# PCB-2x8GPIO.net
KiCad netlist of a schematic drawn in EAGLE
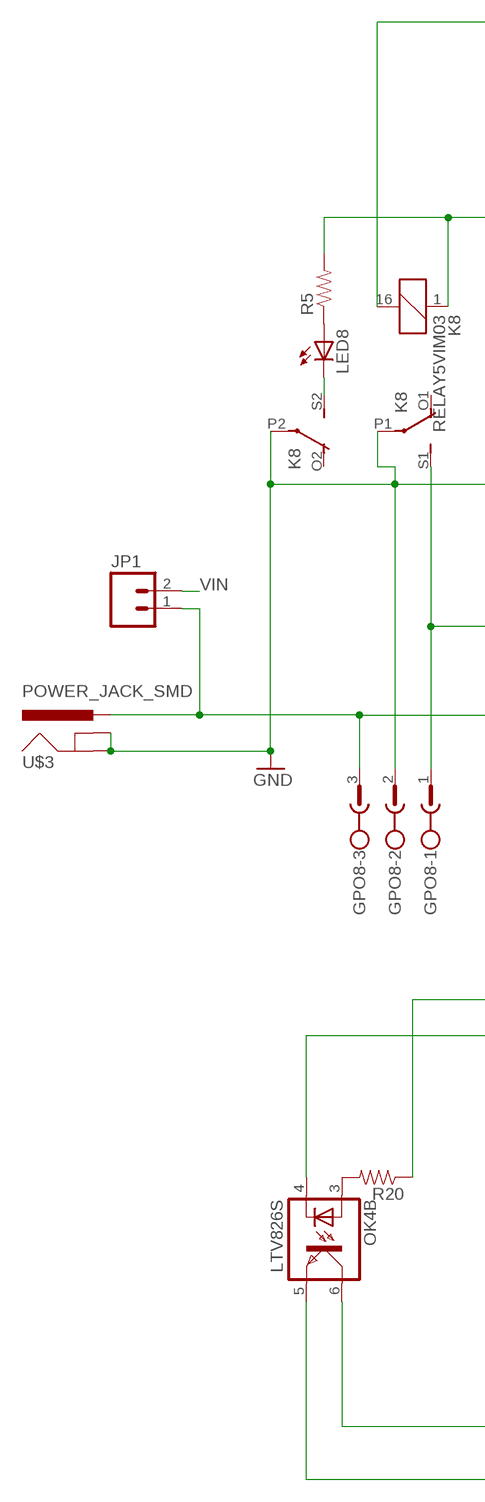
[diagram p0: schematic, sheet 1, part 1 of 2]
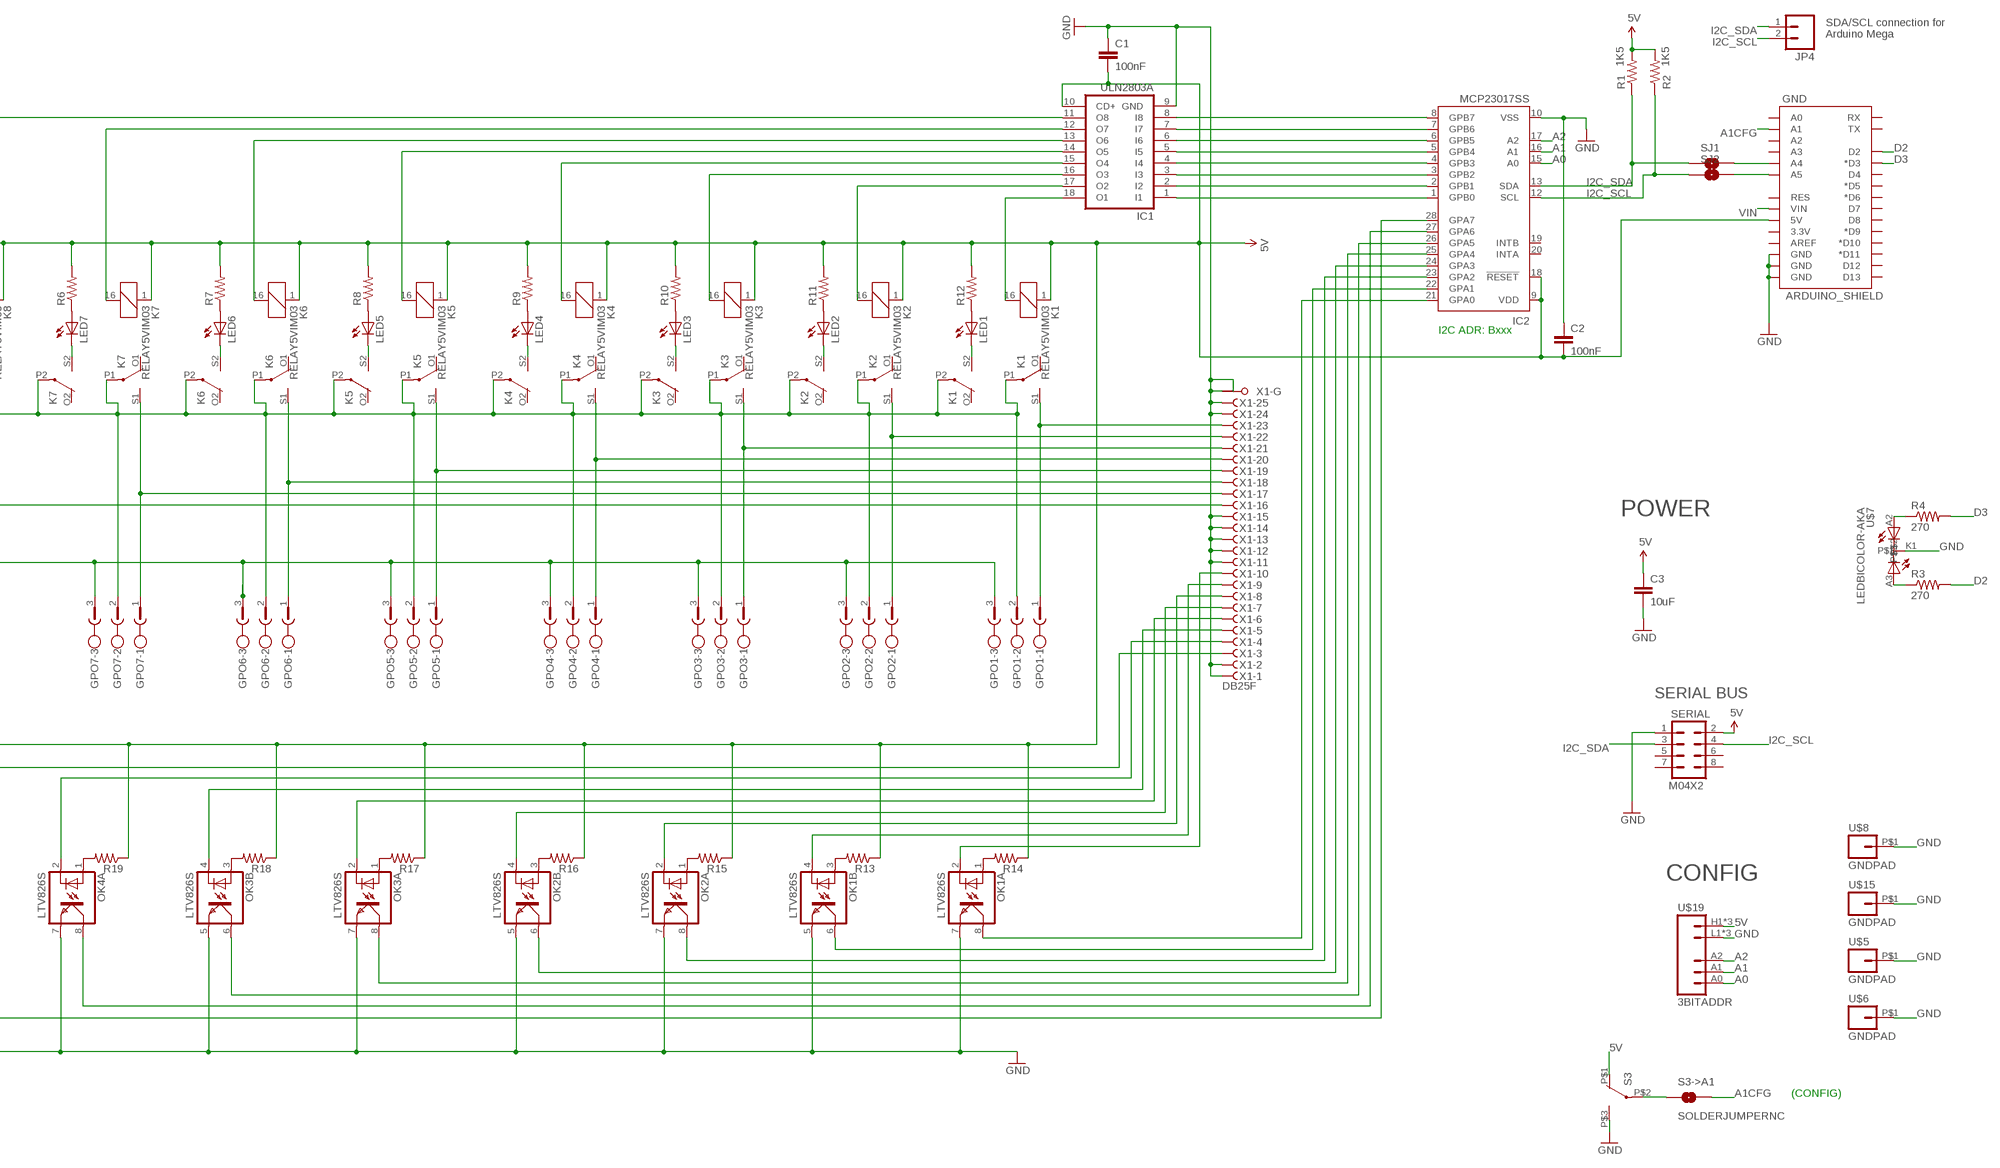
[diagram p1: schematic, sheet 1, part 2 of 2]

(export (version "E")
  (design (tool "Eeschema 10.0.6"))
  (components
    (comp (ref "C1")
      (value "100nF")
      (footprint "eagle-import:0805")
      (libsource (lib "eagle-import") (part "CAP0805"))
    )
    (comp (ref "C2")
      (value "100nF")
      (footprint "eagle-import:0603-CAP")
      (libsource (lib "eagle-import") (part "CAP0603-CAP"))
    )
    (comp (ref "C3")
      (value "10uF")
      (footprint "eagle-import:0805")
      (libsource (lib "eagle-import") (part "CAP0805"))
    )
    (comp (ref "GND")
      (value "ARDUINO_SHIELD")
      (footprint "eagle-import:ARDUINO_BOXSHIELD_NOHOLES")
      (libsource (lib "eagle-import") (part "ARDUINO_SHIELD"))
    )
    (comp (ref "GPO1")
      (value "CON1")
      (footprint "eagle-import:MSTBV3")
      (fields (field (name "MPN") "MSTBV 2,5/3-GF-5.08"))
      (libsource (lib "eagle-import") (part "MSTBV3"))
    )
    (comp (ref "GPO2")
      (value "CON1")
      (footprint "eagle-import:MSTBV3")
      (fields (field (name "MPN") "MSTBV 2,5/3-GF-5.08"))
      (libsource (lib "eagle-import") (part "MSTBV3"))
    )
    (comp (ref "GPO3")
      (value "CON1")
      (footprint "eagle-import:MSTBV3")
      (fields (field (name "MPN") "MSTBV 2,5/3-GF-5.08"))
      (libsource (lib "eagle-import") (part "MSTBV3"))
    )
    (comp (ref "GPO4")
      (value "CON1")
      (footprint "eagle-import:MSTBV3")
      (fields (field (name "MPN") "MSTBV 2,5/3-GF-5.08"))
      (libsource (lib "eagle-import") (part "MSTBV3"))
    )
    (comp (ref "GPO5")
      (value "CON1")
      (footprint "eagle-import:MSTBV3")
      (fields (field (name "MPN") "MSTBV 2,5/3-GF-5.08"))
      (libsource (lib "eagle-import") (part "MSTBV3"))
    )
    (comp (ref "GPO6")
      (value "CON1")
      (footprint "eagle-import:MSTBV3")
      (fields (field (name "MPN") "MSTBV 2,5/3-GF-5.08"))
      (libsource (lib "eagle-import") (part "MSTBV3"))
    )
    (comp (ref "GPO7")
      (value "CON1")
      (footprint "eagle-import:MSTBV3")
      (fields (field (name "MPN") "MSTBV 2,5/3-GF-5.08"))
      (libsource (lib "eagle-import") (part "MSTBV3"))
    )
    (comp (ref "GPO8")
      (value "GPO8")
      (footprint "eagle-import:MSTBV3")
      (fields (field (name "MPN") "MSTBV 2,5/3-GF-5.08"))
      (libsource (lib "eagle-import") (part "MSTBV3"))
    )
    (comp (ref "IC1")
      (value "ULN2803A")
      (footprint "eagle-import:SO18W")
      (libsource (lib "eagle-import") (part "ULN2803ASO18W"))
    )
    (comp (ref "IC2")
      (value "MCP23017SS")
      (footprint "eagle-import:SSOP28")
      (fields (field (name "MF") "MICROCHIP") (field (name "MPN") "MCP23017-E/SS"))
      (libsource (lib "eagle-import") (part "MCP23017SS"))
    )
    (comp (ref "JP1")
      (value "M02LOCK")
      (footprint "eagle-import:1X02_LOCK")
      (libsource (lib "eagle-import") (part "M02LOCK"))
    )
    (comp (ref "JP4")
      (value "M02PTH")
      (footprint "eagle-import:1X02")
      (libsource (lib "eagle-import") (part "M02PTH"))
    )
    (comp (ref "K1")
      (value "RELAY5VIM03")
      (footprint "eagle-import:DS2Y")
      (libsource (lib "eagle-import") (part "RELAY5VIM03"))
    )
    (comp (ref "K2")
      (value "RELAY5VIM03")
      (footprint "eagle-import:DS2Y")
      (libsource (lib "eagle-import") (part "RELAY5VIM03"))
    )
    (comp (ref "K3")
      (value "RELAY5VIM03")
      (footprint "eagle-import:DS2Y")
      (libsource (lib "eagle-import") (part "RELAY5VIM03"))
    )
    (comp (ref "K4")
      (value "RELAY5VIM03")
      (footprint "eagle-import:DS2Y")
      (libsource (lib "eagle-import") (part "RELAY5VIM03"))
    )
    (comp (ref "K5")
      (value "RELAY5VIM03")
      (footprint "eagle-import:DS2Y")
      (libsource (lib "eagle-import") (part "RELAY5VIM03"))
    )
    (comp (ref "K6")
      (value "RELAY5VIM03")
      (footprint "eagle-import:DS2Y")
      (libsource (lib "eagle-import") (part "RELAY5VIM03"))
    )
    (comp (ref "K7")
      (value "RELAY5VIM03")
      (footprint "eagle-import:DS2Y")
      (libsource (lib "eagle-import") (part "RELAY5VIM03"))
    )
    (comp (ref "K8")
      (value "RELAY5VIM03")
      (footprint "eagle-import:DS2Y")
      (libsource (lib "eagle-import") (part "RELAY5VIM03"))
    )
    (comp (ref "LED1")
      (value "LED1206")
      (footprint "eagle-import:LED-1206")
      (libsource (lib "eagle-import") (part "LED1206"))
    )
    (comp (ref "LED2")
      (value "LED1206")
      (footprint "eagle-import:LED-1206")
      (libsource (lib "eagle-import") (part "LED1206"))
    )
    (comp (ref "LED3")
      (value "LED1206")
      (footprint "eagle-import:LED-1206")
      (libsource (lib "eagle-import") (part "LED1206"))
    )
    (comp (ref "LED4")
      (value "LED1206")
      (footprint "eagle-import:LED-1206")
      (libsource (lib "eagle-import") (part "LED1206"))
    )
    (comp (ref "LED5")
      (value "LED1206")
      (footprint "eagle-import:LED-1206")
      (libsource (lib "eagle-import") (part "LED1206"))
    )
    (comp (ref "LED6")
      (value "LED1206")
      (footprint "eagle-import:LED-1206")
      (libsource (lib "eagle-import") (part "LED1206"))
    )
    (comp (ref "LED7")
      (value "LED1206")
      (footprint "eagle-import:LED-1206")
      (libsource (lib "eagle-import") (part "LED1206"))
    )
    (comp (ref "LED8")
      (value "LED1206")
      (footprint "eagle-import:LED-1206")
      (libsource (lib "eagle-import") (part "LED1206"))
    )
    (comp (ref "OK1")
      (value "LTV826S")
      (footprint "eagle-import:DIL8-SMD")
      (libsource (lib "eagle-import") (part "LTV826S"))
    )
    (comp (ref "OK2")
      (value "LTV826S")
      (footprint "eagle-import:DIL8-SMD")
      (libsource (lib "eagle-import") (part "LTV826S"))
    )
    (comp (ref "OK3")
      (value "LTV826S")
      (footprint "eagle-import:DIL8-SMD")
      (libsource (lib "eagle-import") (part "LTV826S"))
    )
    (comp (ref "OK4")
      (value "LTV826S")
      (footprint "eagle-import:DIL8-SMD")
      (libsource (lib "eagle-import") (part "LTV826S"))
    )
    (comp (ref "R1")
      (value "1K5")
      (footprint "eagle-import:0603-RES")
      (libsource (lib "eagle-import") (part "RESISTOR0603-RES"))
    )
    (comp (ref "R2")
      (value "1K5")
      (footprint "eagle-import:0603-RES")
      (libsource (lib "eagle-import") (part "RESISTOR0603-RES"))
    )
    (comp (ref "R3")
      (value "270")
      (footprint "eagle-import:0603-RES")
      (libsource (lib "eagle-import") (part "RESISTOR0603-RES"))
    )
    (comp (ref "R4")
      (value "270")
      (footprint "eagle-import:0603-RES")
      (libsource (lib "eagle-import") (part "RESISTOR0603-RES"))
    )
    (comp (ref "R5")
      (value "RESISTOR0603-RES")
      (footprint "eagle-import:0603-RES")
      (libsource (lib "eagle-import") (part "RESISTOR0603-RES"))
    )
    (comp (ref "R6")
      (value "RESISTOR0603-RES")
      (footprint "eagle-import:0603-RES")
      (libsource (lib "eagle-import") (part "RESISTOR0603-RES"))
    )
    (comp (ref "R7")
      (value "RESISTOR0603-RES")
      (footprint "eagle-import:0603-RES")
      (libsource (lib "eagle-import") (part "RESISTOR0603-RES"))
    )
    (comp (ref "R8")
      (value "RESISTOR0603-RES")
      (footprint "eagle-import:0603-RES")
      (libsource (lib "eagle-import") (part "RESISTOR0603-RES"))
    )
    (comp (ref "R9")
      (value "RESISTOR0603-RES")
      (footprint "eagle-import:0603-RES")
      (libsource (lib "eagle-import") (part "RESISTOR0603-RES"))
    )
    (comp (ref "R10")
      (value "RESISTOR0603-RES")
      (footprint "eagle-import:0603-RES")
      (libsource (lib "eagle-import") (part "RESISTOR0603-RES"))
    )
    (comp (ref "R11")
      (value "RESISTOR0603-RES")
      (footprint "eagle-import:0603-RES")
      (libsource (lib "eagle-import") (part "RESISTOR0603-RES"))
    )
    (comp (ref "R12")
      (value "RESISTOR0603-RES")
      (footprint "eagle-import:0603-RES")
      (libsource (lib "eagle-import") (part "RESISTOR0603-RES"))
    )
    (comp (ref "R13")
      (value "RESISTOR0603-RES")
      (footprint "eagle-import:0603-RES")
      (libsource (lib "eagle-import") (part "RESISTOR0603-RES"))
    )
    (comp (ref "R14")
      (value "RESISTOR0603-RES")
      (footprint "eagle-import:0603-RES")
      (libsource (lib "eagle-import") (part "RESISTOR0603-RES"))
    )
    (comp (ref "R15")
      (value "RESISTOR0603-RES")
      (footprint "eagle-import:0603-RES")
      (libsource (lib "eagle-import") (part "RESISTOR0603-RES"))
    )
    (comp (ref "R16")
      (value "RESISTOR0603-RES")
      (footprint "eagle-import:0603-RES")
      (libsource (lib "eagle-import") (part "RESISTOR0603-RES"))
    )
    (comp (ref "R17")
      (value "RESISTOR0603-RES")
      (footprint "eagle-import:0603-RES")
      (libsource (lib "eagle-import") (part "RESISTOR0603-RES"))
    )
    (comp (ref "R18")
      (value "RESISTOR0603-RES")
      (footprint "eagle-import:0603-RES")
      (libsource (lib "eagle-import") (part "RESISTOR0603-RES"))
    )
    (comp (ref "R19")
      (value "RESISTOR0603-RES")
      (footprint "eagle-import:0603-RES")
      (libsource (lib "eagle-import") (part "RESISTOR0603-RES"))
    )
    (comp (ref "R20")
      (value "RESISTOR0603-RES")
      (footprint "eagle-import:0603-RES")
      (libsource (lib "eagle-import") (part "RESISTOR0603-RES"))
    )
    (comp (ref "S3")
      (value "CFG")
      (footprint "eagle-import:TECONNECTIVITY-DPST")
      (libsource (lib "eagle-import") (part "SWITCH-DPST"))
    )
    (comp (ref "S3->A1")
      (value "SOLDERJUMPERNC")
      (footprint "eagle-import:SJ_2S")
      (libsource (lib "eagle-import") (part "SOLDERJUMPERNC"))
    )
    (comp (ref "SERIAL")
      (value "M04X2")
      (footprint "eagle-import:2X4")
      (libsource (lib "eagle-import") (part "M04X2"))
    )
    (comp (ref "SJ1")
      (value "SOLDERJUMPERNC")
      (footprint "eagle-import:SJ_2S")
      (libsource (lib "eagle-import") (part "SOLDERJUMPERNC"))
    )
    (comp (ref "SJ2")
      (value "SOLDERJUMPERNC")
      (footprint "eagle-import:SJ_2S")
      (libsource (lib "eagle-import") (part "SOLDERJUMPERNC"))
    )
    (comp (ref "U$3")
      (value "POWER_JACK_SMD")
      (footprint "eagle-import:POWER_JACK_SMD")
      (libsource (lib "eagle-import") (part "POWER_JACK_SMD"))
    )
    (comp (ref "U$5")
      (value "GNDPAD")
      (footprint "eagle-import:3.2MMPAD")
      (libsource (lib "eagle-import") (part "GNDPAD"))
    )
    (comp (ref "U$6")
      (value "GNDPAD")
      (footprint "eagle-import:3.2MMPAD")
      (libsource (lib "eagle-import") (part "GNDPAD"))
    )
    (comp (ref "U$7")
      (value "LEDBICOLOR-AKA")
      (footprint "eagle-import:LED5MM-BICOLOR")
      (libsource (lib "eagle-import") (part "LEDBICOLOR-AKA"))
    )
    (comp (ref "U$8")
      (value "GNDPAD")
      (footprint "eagle-import:3.2MMPAD")
      (libsource (lib "eagle-import") (part "GNDPAD"))
    )
    (comp (ref "U$15")
      (value "GNDPAD")
      (footprint "eagle-import:3.2MMPAD")
      (libsource (lib "eagle-import") (part "GNDPAD"))
    )
    (comp (ref "U$19")
      (value "3BITADDR")
      (footprint "eagle-import:3BITADDR")
      (libsource (lib "eagle-import") (part "3BITADDR"))
    )
    (comp (ref "X1")
      (value "DB25F")
      (footprint "eagle-import:F25HP")
      (libsource (lib "eagle-import") (part "F25HPS"))
    )
  )
  (nets
    (net (code "1") (name "/A0") (class "Default")
      (node (ref "IC2") (pin "15") (pinfunction "A0_15") (pintype "input"))
      (node (ref "U$19") (pin "A0") (pinfunction "A0_A0") (pintype "passive"))
    )
    (net (code "2") (name "/A1") (class "Default")
      (node (ref "IC2") (pin "16") (pinfunction "A1_16") (pintype "input"))
      (node (ref "U$19") (pin "A1") (pinfunction "A1_A1") (pintype "passive"))
    )
    (net (code "3") (name "/A1CFG") (class "Default")
      (node (ref "GND") (pin "A1") (pinfunction "A1_A1") (pintype "bidirectional"))
      (node (ref "S3->A1") (pin "2") (pinfunction "2_2") (pintype "passive"))
    )
    (net (code "4") (name "/A2") (class "Default")
      (node (ref "IC2") (pin "17") (pinfunction "A2_17") (pintype "input"))
      (node (ref "U$19") (pin "A2") (pinfunction "A2_A2") (pintype "passive"))
    )
    (net (code "5") (name "/D2") (class "Default")
      (node (ref "GND") (pin "2") (pinfunction "D2_2") (pintype "bidirectional"))
      (node (ref "R3") (pin "2") (pinfunction "2_2") (pintype "passive"))
    )
    (net (code "6") (name "/D3") (class "Default")
      (node (ref "GND") (pin "3") (pinfunction "*D3_3") (pintype "bidirectional"))
      (node (ref "R4") (pin "2") (pinfunction "2_2") (pintype "passive"))
    )
    (net (code "7") (name "/I2C_SCL") (class "Default")
      (node (ref "IC2") (pin "12") (pinfunction "SCL_12") (pintype "input"))
      (node (ref "JP4") (pin "2") (pinfunction "2_2") (pintype "passive"))
      (node (ref "R2") (pin "1") (pinfunction "1_1") (pintype "passive"))
      (node (ref "SERIAL") (pin "4") (pinfunction "4_4") (pintype "passive"))
      (node (ref "SJ2") (pin "1") (pinfunction "1_1") (pintype "passive"))
    )
    (net (code "8") (name "/I2C_SDA") (class "Default")
      (node (ref "IC2") (pin "13") (pinfunction "SDA_13") (pintype "bidirectional"))
      (node (ref "JP4") (pin "1") (pinfunction "1_1") (pintype "passive"))
      (node (ref "R1") (pin "1") (pinfunction "1_1") (pintype "passive"))
      (node (ref "SERIAL") (pin "3") (pinfunction "3_3") (pintype "passive"))
      (node (ref "SJ1") (pin "1") (pinfunction "1_1") (pintype "passive"))
    )
    (net (code "9") (name "/VIN") (class "Default")
      (node (ref "GND") (pin "VIN") (pinfunction "VIN_VIN") (pintype "bidirectional"))
      (node (ref "JP1") (pin "2") (pinfunction "2_2") (pintype "passive"))
    )
    (net (code "10") (name "5V") (class "Default")
      (node (ref "C1") (pin "2") (pinfunction "2_2") (pintype "passive"))
      (node (ref "C2") (pin "2") (pinfunction "2_2") (pintype "passive"))
      (node (ref "C3") (pin "1") (pinfunction "1_1") (pintype "passive"))
      (node (ref "GND") (pin "5V@0") (pinfunction "5V_5V@0") (pintype "bidirectional"))
      (node (ref "IC1") (pin "10") (pinfunction "CD+_10") (pintype "passive"))
      (node (ref "IC2") (pin "18") (pinfunction "~{RESET}_18") (pintype "input"))
      (node (ref "IC2") (pin "9") (pinfunction "VDD_9") (pintype "power_in"))
      (node (ref "K1") (pin "1") (pinfunction "1_1") (pintype "passive"))
      (node (ref "K2") (pin "1") (pinfunction "1_1") (pintype "passive"))
      (node (ref "K3") (pin "1") (pinfunction "1_1") (pintype "passive"))
      (node (ref "K4") (pin "1") (pinfunction "1_1") (pintype "passive"))
      (node (ref "K5") (pin "1") (pinfunction "1_1") (pintype "passive"))
      (node (ref "K6") (pin "1") (pinfunction "1_1") (pintype "passive"))
      (node (ref "K7") (pin "1") (pinfunction "1_1") (pintype "passive"))
      (node (ref "K8") (pin "1") (pinfunction "1_1") (pintype "passive"))
      (node (ref "R1") (pin "2") (pinfunction "2_2") (pintype "passive"))
      (node (ref "R10") (pin "2") (pinfunction "2_2") (pintype "passive"))
      (node (ref "R11") (pin "2") (pinfunction "2_2") (pintype "passive"))
      (node (ref "R12") (pin "2") (pinfunction "2_2") (pintype "passive"))
      (node (ref "R13") (pin "1") (pinfunction "1_1") (pintype "passive"))
      (node (ref "R14") (pin "1") (pinfunction "1_1") (pintype "passive"))
      (node (ref "R15") (pin "1") (pinfunction "1_1") (pintype "passive"))
      (node (ref "R16") (pin "1") (pinfunction "1_1") (pintype "passive"))
      (node (ref "R17") (pin "1") (pinfunction "1_1") (pintype "passive"))
      (node (ref "R18") (pin "1") (pinfunction "1_1") (pintype "passive"))
      (node (ref "R19") (pin "1") (pinfunction "1_1") (pintype "passive"))
      (node (ref "R2") (pin "2") (pinfunction "2_2") (pintype "passive"))
      (node (ref "R20") (pin "1") (pinfunction "1_1") (pintype "passive"))
      (node (ref "R5") (pin "2") (pinfunction "2_2") (pintype "passive"))
      (node (ref "R6") (pin "2") (pinfunction "2_2") (pintype "passive"))
      (node (ref "R7") (pin "2") (pinfunction "2_2") (pintype "passive"))
      (node (ref "R8") (pin "2") (pinfunction "2_2") (pintype "passive"))
      (node (ref "R9") (pin "2") (pinfunction "2_2") (pintype "passive"))
      (node (ref "S3") (pin "P$1") (pinfunction "O_P$1") (pintype "passive"))
      (node (ref "SERIAL") (pin "2") (pinfunction "2_2") (pintype "passive"))
      (node (ref "U$19") (pin "H1") (pinfunction "VCC_H1") (pintype "passive"))
      (node (ref "U$19") (pin "H2") (pinfunction "VCC_H2") (pintype "passive"))
      (node (ref "U$19") (pin "H3") (pinfunction "VCC_H3") (pintype "passive"))
    )
    (net (code "11") (name "GND") (class "Default")
      (node (ref "C1") (pin "1") (pinfunction "1_1") (pintype "passive"))
      (node (ref "C2") (pin "1") (pinfunction "1_1") (pintype "passive"))
      (node (ref "C3") (pin "2") (pinfunction "2_2") (pintype "passive"))
      (node (ref "GND") (pin "GND@0") (pinfunction "GND_GND@0") (pintype "bidirectional"))
      (node (ref "GND") (pin "GND@1") (pinfunction "GND_GND@1") (pintype "bidirectional"))
      (node (ref "GND") (pin "GND@4") (pinfunction "GND_GND@4") (pintype "bidirectional"))
      (node (ref "GPO1") (pin "2") (pinfunction "1_2") (pintype "passive"))
      (node (ref "GPO2") (pin "2") (pinfunction "1_2") (pintype "passive"))
      (node (ref "GPO3") (pin "2") (pinfunction "1_2") (pintype "passive"))
      (node (ref "GPO4") (pin "2") (pinfunction "1_2") (pintype "passive"))
      (node (ref "GPO5") (pin "2") (pinfunction "1_2") (pintype "passive"))
      (node (ref "GPO6") (pin "2") (pinfunction "1_2") (pintype "passive"))
      (node (ref "GPO7") (pin "2") (pinfunction "1_2") (pintype "passive"))
      (node (ref "GPO8") (pin "2") (pinfunction "1_2") (pintype "passive"))
      (node (ref "IC1") (pin "9") (pinfunction "GND_9") (pintype "power_in"))
      (node (ref "IC2") (pin "10") (pinfunction "VSS_10") (pintype "power_in"))
      (node (ref "K1") (pin "P1") (pinfunction "P_P1") (pintype "passive"))
      (node (ref "K1") (pin "P2") (pinfunction "P_P2") (pintype "passive"))
      (node (ref "K2") (pin "P1") (pinfunction "P_P1") (pintype "passive"))
      (node (ref "K2") (pin "P2") (pinfunction "P_P2") (pintype "passive"))
      (node (ref "K3") (pin "P1") (pinfunction "P_P1") (pintype "passive"))
      (node (ref "K3") (pin "P2") (pinfunction "P_P2") (pintype "passive"))
      (node (ref "K4") (pin "P1") (pinfunction "P_P1") (pintype "passive"))
      (node (ref "K4") (pin "P2") (pinfunction "P_P2") (pintype "passive"))
      (node (ref "K5") (pin "P1") (pinfunction "P_P1") (pintype "passive"))
      (node (ref "K5") (pin "P2") (pinfunction "P_P2") (pintype "passive"))
      (node (ref "K6") (pin "P1") (pinfunction "P_P1") (pintype "passive"))
      (node (ref "K6") (pin "P2") (pinfunction "P_P2") (pintype "passive"))
      (node (ref "K7") (pin "P1") (pinfunction "P_P1") (pintype "passive"))
      (node (ref "K7") (pin "P2") (pinfunction "P_P2") (pintype "passive"))
      (node (ref "K8") (pin "P1") (pinfunction "P_P1") (pintype "passive"))
      (node (ref "K8") (pin "P2") (pinfunction "P_P2") (pintype "passive"))
      (node (ref "OK1") (pin "5") (pinfunction "EMIT_5") (pintype "passive"))
      (node (ref "OK1") (pin "7") (pinfunction "EMIT_7") (pintype "passive"))
      (node (ref "OK2") (pin "5") (pinfunction "EMIT_5") (pintype "passive"))
      (node (ref "OK2") (pin "7") (pinfunction "EMIT_7") (pintype "passive"))
      (node (ref "OK3") (pin "5") (pinfunction "EMIT_5") (pintype "passive"))
      (node (ref "OK3") (pin "7") (pinfunction "EMIT_7") (pintype "passive"))
      (node (ref "OK4") (pin "5") (pinfunction "EMIT_5") (pintype "passive"))
      (node (ref "OK4") (pin "7") (pinfunction "EMIT_7") (pintype "passive"))
      (node (ref "S3") (pin "P$3") (pinfunction "S_P$3") (pintype "passive"))
      (node (ref "SERIAL") (pin "1") (pinfunction "1_1") (pintype "passive"))
      (node (ref "U$15") (pin "P$1") (pinfunction "1_P$1") (pintype "passive"))
      (node (ref "U$19") (pin "L1") (pinfunction "GND_L1") (pintype "passive"))
      (node (ref "U$19") (pin "L2") (pinfunction "GND_L2") (pintype "passive"))
      (node (ref "U$19") (pin "L3") (pinfunction "GND_L3") (pintype "passive"))
      (node (ref "U$3") (pin "GND") (pinfunction "GND_GND") (pintype "bidirectional"))
      (node (ref "U$3") (pin "SHUNT") (pinfunction "GNDBREAK_SHUNT") (pintype "bidirectional"))
      (node (ref "U$5") (pin "P$1") (pinfunction "1_P$1") (pintype "passive"))
      (node (ref "U$6") (pin "P$1") (pinfunction "1_P$1") (pintype "passive"))
      (node (ref "U$7") (pin "K1") (pinfunction "P$1_K1") (pintype "bidirectional"))
      (node (ref "U$8") (pin "P$1") (pinfunction "1_P$1") (pintype "passive"))
      (node (ref "X1") (pin "1") (pinfunction "F_1") (pintype "passive"))
      (node (ref "X1") (pin "11") (pinfunction "F_11") (pintype "passive"))
      (node (ref "X1") (pin "12") (pinfunction "F_12") (pintype "passive"))
      (node (ref "X1") (pin "13") (pinfunction "F_13") (pintype "passive"))
      (node (ref "X1") (pin "14") (pinfunction "F_14") (pintype "passive"))
      (node (ref "X1") (pin "15") (pinfunction "F_15") (pintype "passive"))
      (node (ref "X1") (pin "2") (pinfunction "F_2") (pintype "passive"))
      (node (ref "X1") (pin "24") (pinfunction "F_24") (pintype "passive"))
      (node (ref "X1") (pin "25") (pinfunction "F_25") (pintype "passive"))
      (node (ref "X1") (pin "G1") (pinfunction "G1_G1") (pintype "passive"))
      (node (ref "X1") (pin "G2") (pinfunction "G2_G2") (pintype "passive"))
    )
    (net (code "12") (name "Net-(GND-PadA4)") (class "Default")
      (node (ref "GND") (pin "A4") (pinfunction "A4_A4") (pintype "bidirectional"))
      (node (ref "SJ1") (pin "2") (pinfunction "2_2") (pintype "passive"))
    )
    (net (code "13") (name "Net-(GND-PadA5)") (class "Default")
      (node (ref "GND") (pin "A5") (pinfunction "A5_A5") (pintype "bidirectional"))
      (node (ref "SJ2") (pin "2") (pinfunction "2_2") (pintype "passive"))
    )
    (net (code "14") (name "Net-(GPO1C-1)") (class "Default")
      (node (ref "GPO1") (pin "3") (pinfunction "1_3") (pintype "passive"))
      (node (ref "GPO2") (pin "3") (pinfunction "1_3") (pintype "passive"))
      (node (ref "GPO3") (pin "3") (pinfunction "1_3") (pintype "passive"))
      (node (ref "GPO4") (pin "3") (pinfunction "1_3") (pintype "passive"))
      (node (ref "GPO5") (pin "3") (pinfunction "1_3") (pintype "passive"))
      (node (ref "GPO6") (pin "3") (pinfunction "1_3") (pintype "passive"))
      (node (ref "GPO7") (pin "3") (pinfunction "1_3") (pintype "passive"))
      (node (ref "GPO8") (pin "3") (pinfunction "1_3") (pintype "passive"))
      (node (ref "JP1") (pin "1") (pinfunction "1_1") (pintype "passive"))
      (node (ref "U$3") (pin "PWR") (pinfunction "PWR_PWR") (pintype "bidirectional"))
    )
    (net (code "15") (name "Net-(IC1-I1)") (class "Default")
      (node (ref "IC1") (pin "1") (pinfunction "I1_1") (pintype "input"))
      (node (ref "IC2") (pin "1") (pinfunction "GPB0_1") (pintype "bidirectional"))
    )
    (net (code "16") (name "Net-(IC1-I2)") (class "Default")
      (node (ref "IC1") (pin "2") (pinfunction "I2_2") (pintype "input"))
      (node (ref "IC2") (pin "2") (pinfunction "GPB1_2") (pintype "bidirectional"))
    )
    (net (code "17") (name "Net-(IC1-I3)") (class "Default")
      (node (ref "IC1") (pin "3") (pinfunction "I3_3") (pintype "input"))
      (node (ref "IC2") (pin "3") (pinfunction "GPB2_3") (pintype "bidirectional"))
    )
    (net (code "18") (name "Net-(IC1-I4)") (class "Default")
      (node (ref "IC1") (pin "4") (pinfunction "I4_4") (pintype "input"))
      (node (ref "IC2") (pin "4") (pinfunction "GPB3_4") (pintype "bidirectional"))
    )
    (net (code "19") (name "Net-(IC1-I5)") (class "Default")
      (node (ref "IC1") (pin "5") (pinfunction "I5_5") (pintype "input"))
      (node (ref "IC2") (pin "5") (pinfunction "GPB4_5") (pintype "bidirectional"))
    )
    (net (code "20") (name "Net-(IC1-I6)") (class "Default")
      (node (ref "IC1") (pin "6") (pinfunction "I6_6") (pintype "input"))
      (node (ref "IC2") (pin "6") (pinfunction "GPB5_6") (pintype "bidirectional"))
    )
    (net (code "21") (name "Net-(IC1-I7)") (class "Default")
      (node (ref "IC1") (pin "7") (pinfunction "I7_7") (pintype "input"))
      (node (ref "IC2") (pin "7") (pinfunction "GPB6_7") (pintype "bidirectional"))
    )
    (net (code "22") (name "Net-(IC1-I8)") (class "Default")
      (node (ref "IC1") (pin "8") (pinfunction "I8_8") (pintype "input"))
      (node (ref "IC2") (pin "8") (pinfunction "GPB7_8") (pintype "bidirectional"))
    )
    (net (code "23") (name "Net-(IC1-O1)") (class "Default")
      (node (ref "IC1") (pin "18") (pinfunction "O1_18") (pintype "open_collector"))
      (node (ref "K1") (pin "16") (pinfunction "2_16") (pintype "passive"))
    )
    (net (code "24") (name "Net-(IC1-O2)") (class "Default")
      (node (ref "IC1") (pin "17") (pinfunction "O2_17") (pintype "open_collector"))
      (node (ref "K2") (pin "16") (pinfunction "2_16") (pintype "passive"))
    )
    (net (code "25") (name "Net-(IC1-O3)") (class "Default")
      (node (ref "IC1") (pin "16") (pinfunction "O3_16") (pintype "open_collector"))
      (node (ref "K3") (pin "16") (pinfunction "2_16") (pintype "passive"))
    )
    (net (code "26") (name "Net-(IC1-O4)") (class "Default")
      (node (ref "IC1") (pin "15") (pinfunction "O4_15") (pintype "open_collector"))
      (node (ref "K4") (pin "16") (pinfunction "2_16") (pintype "passive"))
    )
    (net (code "27") (name "Net-(IC1-O5)") (class "Default")
      (node (ref "IC1") (pin "14") (pinfunction "O5_14") (pintype "open_collector"))
      (node (ref "K5") (pin "16") (pinfunction "2_16") (pintype "passive"))
    )
    (net (code "28") (name "Net-(IC1-O6)") (class "Default")
      (node (ref "IC1") (pin "13") (pinfunction "O6_13") (pintype "open_collector"))
      (node (ref "K6") (pin "16") (pinfunction "2_16") (pintype "passive"))
    )
    (net (code "29") (name "Net-(IC1-O7)") (class "Default")
      (node (ref "IC1") (pin "12") (pinfunction "O7_12") (pintype "open_collector"))
      (node (ref "K7") (pin "16") (pinfunction "2_16") (pintype "passive"))
    )
    (net (code "30") (name "Net-(IC1-O8)") (class "Default")
      (node (ref "IC1") (pin "11") (pinfunction "O8_11") (pintype "open_collector"))
      (node (ref "K8") (pin "16") (pinfunction "2_16") (pintype "passive"))
    )
    (net (code "31") (name "Net-(IC2-GPA0)") (class "Default")
      (node (ref "IC2") (pin "21") (pinfunction "GPA0_21") (pintype "bidirectional"))
      (node (ref "OK1") (pin "8") (pinfunction "COL_8") (pintype "passive"))
    )
    (net (code "32") (name "Net-(IC2-GPA1)") (class "Default")
      (node (ref "IC2") (pin "22") (pinfunction "GPA1_22") (pintype "bidirectional"))
      (node (ref "OK1") (pin "6") (pinfunction "COL_6") (pintype "passive"))
    )
    (net (code "33") (name "Net-(IC2-GPA2)") (class "Default")
      (node (ref "IC2") (pin "23") (pinfunction "GPA2_23") (pintype "bidirectional"))
      (node (ref "OK2") (pin "8") (pinfunction "COL_8") (pintype "passive"))
    )
    (net (code "34") (name "Net-(IC2-GPA3)") (class "Default")
      (node (ref "IC2") (pin "24") (pinfunction "GPA3_24") (pintype "bidirectional"))
      (node (ref "OK2") (pin "6") (pinfunction "COL_6") (pintype "passive"))
    )
    (net (code "35") (name "Net-(IC2-GPA4)") (class "Default")
      (node (ref "IC2") (pin "25") (pinfunction "GPA4_25") (pintype "bidirectional"))
      (node (ref "OK3") (pin "8") (pinfunction "COL_8") (pintype "passive"))
    )
    (net (code "36") (name "Net-(IC2-GPA5)") (class "Default")
      (node (ref "IC2") (pin "26") (pinfunction "GPA5_26") (pintype "bidirectional"))
      (node (ref "OK3") (pin "6") (pinfunction "COL_6") (pintype "passive"))
    )
    (net (code "37") (name "Net-(IC2-GPA6)") (class "Default")
      (node (ref "IC2") (pin "27") (pinfunction "GPA6_27") (pintype "bidirectional"))
      (node (ref "OK4") (pin "8") (pinfunction "COL_8") (pintype "passive"))
    )
    (net (code "38") (name "Net-(IC2-GPA7)") (class "Default")
      (node (ref "IC2") (pin "28") (pinfunction "GPA7_28") (pintype "bidirectional"))
      (node (ref "OK4") (pin "6") (pinfunction "COL_6") (pintype "passive"))
    )
    (net (code "39") (name "Net-(K1B-S)") (class "Default")
      (node (ref "GPO1") (pin "1") (pinfunction "1_1") (pintype "passive"))
      (node (ref "K1") (pin "S1") (pinfunction "S_S1") (pintype "passive"))
      (node (ref "X1") (pin "23") (pinfunction "F_23") (pintype "passive"))
    )
    (net (code "40") (name "Net-(K1C-S)") (class "Default")
      (node (ref "K1") (pin "S2") (pinfunction "S_S2") (pintype "passive"))
      (node (ref "LED1") (pin "C") (pinfunction "C_C") (pintype "passive"))
    )
    (net (code "41") (name "Net-(K2B-S)") (class "Default")
      (node (ref "GPO2") (pin "1") (pinfunction "1_1") (pintype "passive"))
      (node (ref "K2") (pin "S1") (pinfunction "S_S1") (pintype "passive"))
      (node (ref "X1") (pin "22") (pinfunction "F_22") (pintype "passive"))
    )
    (net (code "42") (name "Net-(K2C-S)") (class "Default")
      (node (ref "K2") (pin "S2") (pinfunction "S_S2") (pintype "passive"))
      (node (ref "LED2") (pin "C") (pinfunction "C_C") (pintype "passive"))
    )
    (net (code "43") (name "Net-(K3B-S)") (class "Default")
      (node (ref "GPO3") (pin "1") (pinfunction "1_1") (pintype "passive"))
      (node (ref "K3") (pin "S1") (pinfunction "S_S1") (pintype "passive"))
      (node (ref "X1") (pin "21") (pinfunction "F_21") (pintype "passive"))
    )
    (net (code "44") (name "Net-(K3C-S)") (class "Default")
      (node (ref "K3") (pin "S2") (pinfunction "S_S2") (pintype "passive"))
      (node (ref "LED3") (pin "C") (pinfunction "C_C") (pintype "passive"))
    )
    (net (code "45") (name "Net-(K4B-S)") (class "Default")
      (node (ref "GPO4") (pin "1") (pinfunction "1_1") (pintype "passive"))
      (node (ref "K4") (pin "S1") (pinfunction "S_S1") (pintype "passive"))
      (node (ref "X1") (pin "20") (pinfunction "F_20") (pintype "passive"))
    )
    (net (code "46") (name "Net-(K4C-S)") (class "Default")
      (node (ref "K4") (pin "S2") (pinfunction "S_S2") (pintype "passive"))
      (node (ref "LED4") (pin "C") (pinfunction "C_C") (pintype "passive"))
    )
    (net (code "47") (name "Net-(K5B-S)") (class "Default")
      (node (ref "GPO5") (pin "1") (pinfunction "1_1") (pintype "passive"))
      (node (ref "K5") (pin "S1") (pinfunction "S_S1") (pintype "passive"))
      (node (ref "X1") (pin "19") (pinfunction "F_19") (pintype "passive"))
    )
    (net (code "48") (name "Net-(K5C-S)") (class "Default")
      (node (ref "K5") (pin "S2") (pinfunction "S_S2") (pintype "passive"))
      (node (ref "LED5") (pin "C") (pinfunction "C_C") (pintype "passive"))
    )
    (net (code "49") (name "Net-(K6B-S)") (class "Default")
      (node (ref "GPO6") (pin "1") (pinfunction "1_1") (pintype "passive"))
      (node (ref "K6") (pin "S1") (pinfunction "S_S1") (pintype "passive"))
      (node (ref "X1") (pin "18") (pinfunction "F_18") (pintype "passive"))
    )
    (net (code "50") (name "Net-(K6C-S)") (class "Default")
      (node (ref "K6") (pin "S2") (pinfunction "S_S2") (pintype "passive"))
      (node (ref "LED6") (pin "C") (pinfunction "C_C") (pintype "passive"))
    )
    (net (code "51") (name "Net-(K7B-S)") (class "Default")
      (node (ref "GPO7") (pin "1") (pinfunction "1_1") (pintype "passive"))
      (node (ref "K7") (pin "S1") (pinfunction "S_S1") (pintype "passive"))
      (node (ref "X1") (pin "17") (pinfunction "F_17") (pintype "passive"))
    )
    (net (code "52") (name "Net-(K7C-S)") (class "Default")
      (node (ref "K7") (pin "S2") (pinfunction "S_S2") (pintype "passive"))
      (node (ref "LED7") (pin "C") (pinfunction "C_C") (pintype "passive"))
    )
    (net (code "53") (name "Net-(K8B-S)") (class "Default")
      (node (ref "GPO8") (pin "1") (pinfunction "1_1") (pintype "passive"))
      (node (ref "K8") (pin "S1") (pinfunction "S_S1") (pintype "passive"))
      (node (ref "X1") (pin "16") (pinfunction "F_16") (pintype "passive"))
    )
    (net (code "54") (name "Net-(K8C-S)") (class "Default")
      (node (ref "K8") (pin "S2") (pinfunction "S_S2") (pintype "passive"))
      (node (ref "LED8") (pin "C") (pinfunction "C_C") (pintype "passive"))
    )
    (net (code "55") (name "Net-(LED1-PadA)") (class "Default")
      (node (ref "LED1") (pin "A") (pinfunction "A_A") (pintype "passive"))
      (node (ref "R12") (pin "1") (pinfunction "1_1") (pintype "passive"))
    )
    (net (code "56") (name "Net-(LED2-PadA)") (class "Default")
      (node (ref "LED2") (pin "A") (pinfunction "A_A") (pintype "passive"))
      (node (ref "R11") (pin "1") (pinfunction "1_1") (pintype "passive"))
    )
    (net (code "57") (name "Net-(LED3-PadA)") (class "Default")
      (node (ref "LED3") (pin "A") (pinfunction "A_A") (pintype "passive"))
      (node (ref "R10") (pin "1") (pinfunction "1_1") (pintype "passive"))
    )
    (net (code "58") (name "Net-(LED4-PadA)") (class "Default")
      (node (ref "LED4") (pin "A") (pinfunction "A_A") (pintype "passive"))
      (node (ref "R9") (pin "1") (pinfunction "1_1") (pintype "passive"))
    )
    (net (code "59") (name "Net-(LED5-PadA)") (class "Default")
      (node (ref "LED5") (pin "A") (pinfunction "A_A") (pintype "passive"))
      (node (ref "R8") (pin "1") (pinfunction "1_1") (pintype "passive"))
    )
    (net (code "60") (name "Net-(LED6-PadA)") (class "Default")
      (node (ref "LED6") (pin "A") (pinfunction "A_A") (pintype "passive"))
      (node (ref "R7") (pin "1") (pinfunction "1_1") (pintype "passive"))
    )
    (net (code "61") (name "Net-(LED7-PadA)") (class "Default")
      (node (ref "LED7") (pin "A") (pinfunction "A_A") (pintype "passive"))
      (node (ref "R6") (pin "1") (pinfunction "1_1") (pintype "passive"))
    )
    (net (code "62") (name "Net-(LED8-PadA)") (class "Default")
      (node (ref "LED8") (pin "A") (pinfunction "A_A") (pintype "passive"))
      (node (ref "R5") (pin "1") (pinfunction "1_1") (pintype "passive"))
    )
    (net (code "63") (name "Net-(OK1A-A)") (class "Default")
      (node (ref "OK1") (pin "1") (pinfunction "A_1") (pintype "passive"))
      (node (ref "R14") (pin "2") (pinfunction "2_2") (pintype "passive"))
    )
    (net (code "64") (name "Net-(OK1A-C)") (class "Default")
      (node (ref "OK1") (pin "2") (pinfunction "C_2") (pintype "passive"))
      (node (ref "X1") (pin "10") (pinfunction "F_10") (pintype "passive"))
    )
    (net (code "65") (name "Net-(OK1B-A)") (class "Default")
      (node (ref "OK1") (pin "3") (pinfunction "A_3") (pintype "passive"))
      (node (ref "R13") (pin "2") (pinfunction "2_2") (pintype "passive"))
    )
    (net (code "66") (name "Net-(OK1B-C)") (class "Default")
      (node (ref "OK1") (pin "4") (pinfunction "C_4") (pintype "passive"))
      (node (ref "X1") (pin "9") (pinfunction "F_9") (pintype "passive"))
    )
    (net (code "67") (name "Net-(OK2A-A)") (class "Default")
      (node (ref "OK2") (pin "1") (pinfunction "A_1") (pintype "passive"))
      (node (ref "R15") (pin "2") (pinfunction "2_2") (pintype "passive"))
    )
    (net (code "68") (name "Net-(OK2A-C)") (class "Default")
      (node (ref "OK2") (pin "2") (pinfunction "C_2") (pintype "passive"))
      (node (ref "X1") (pin "8") (pinfunction "F_8") (pintype "passive"))
    )
    (net (code "69") (name "Net-(OK2B-A)") (class "Default")
      (node (ref "OK2") (pin "3") (pinfunction "A_3") (pintype "passive"))
      (node (ref "R16") (pin "2") (pinfunction "2_2") (pintype "passive"))
    )
    (net (code "70") (name "Net-(OK2B-C)") (class "Default")
      (node (ref "OK2") (pin "4") (pinfunction "C_4") (pintype "passive"))
      (node (ref "X1") (pin "7") (pinfunction "F_7") (pintype "passive"))
    )
    (net (code "71") (name "Net-(OK3A-A)") (class "Default")
      (node (ref "OK3") (pin "1") (pinfunction "A_1") (pintype "passive"))
      (node (ref "R17") (pin "2") (pinfunction "2_2") (pintype "passive"))
    )
    (net (code "72") (name "Net-(OK3A-C)") (class "Default")
      (node (ref "OK3") (pin "2") (pinfunction "C_2") (pintype "passive"))
      (node (ref "X1") (pin "6") (pinfunction "F_6") (pintype "passive"))
    )
    (net (code "73") (name "Net-(OK3B-A)") (class "Default")
      (node (ref "OK3") (pin "3") (pinfunction "A_3") (pintype "passive"))
      (node (ref "R18") (pin "2") (pinfunction "2_2") (pintype "passive"))
    )
    (net (code "74") (name "Net-(OK3B-C)") (class "Default")
      (node (ref "OK3") (pin "4") (pinfunction "C_4") (pintype "passive"))
      (node (ref "X1") (pin "5") (pinfunction "F_5") (pintype "passive"))
    )
    (net (code "75") (name "Net-(OK4A-A)") (class "Default")
      (node (ref "OK4") (pin "1") (pinfunction "A_1") (pintype "passive"))
      (node (ref "R19") (pin "2") (pinfunction "2_2") (pintype "passive"))
    )
    (net (code "76") (name "Net-(OK4A-C)") (class "Default")
      (node (ref "OK4") (pin "2") (pinfunction "C_2") (pintype "passive"))
      (node (ref "X1") (pin "4") (pinfunction "F_4") (pintype "passive"))
    )
    (net (code "77") (name "Net-(OK4B-A)") (class "Default")
      (node (ref "OK4") (pin "3") (pinfunction "A_3") (pintype "passive"))
      (node (ref "R20") (pin "2") (pinfunction "2_2") (pintype "passive"))
    )
    (net (code "78") (name "Net-(OK4B-C)") (class "Default")
      (node (ref "OK4") (pin "4") (pinfunction "C_4") (pintype "passive"))
      (node (ref "X1") (pin "3") (pinfunction "F_3") (pintype "passive"))
    )
    (net (code "79") (name "Net-(S3-P)") (class "Default")
      (node (ref "S3") (pin "P$2") (pinfunction "P_P$2") (pintype "passive"))
      (node (ref "S3->A1") (pin "1") (pinfunction "1_1") (pintype "passive"))
    )
    (net (code "80") (name "Net-(U$7-P$2)") (class "Default")
      (node (ref "R4") (pin "1") (pinfunction "1_1") (pintype "passive"))
      (node (ref "U$7") (pin "A2") (pinfunction "P$2_A2") (pintype "bidirectional"))
    )
    (net (code "81") (name "Net-(U$7-P$3)") (class "Default")
      (node (ref "R3") (pin "1") (pinfunction "1_1") (pintype "passive"))
      (node (ref "U$7") (pin "A3") (pinfunction "P$3_A3") (pintype "bidirectional"))
    )
    (net (code "82") (name "unconnected-(GND-*D5-Pad5)") (class "Default")
      (node (ref "GND") (pin "5") (pinfunction "*D5_5") (pintype "bidirectional"))
    )
    (net (code "83") (name "unconnected-(GND-*D6-Pad6)") (class "Default")
      (node (ref "GND") (pin "6") (pinfunction "*D6_6") (pintype "bidirectional"))
    )
    (net (code "84") (name "unconnected-(GND-*D9-Pad9)") (class "Default")
      (node (ref "GND") (pin "9") (pinfunction "*D9_9") (pintype "bidirectional"))
    )
    (net (code "85") (name "unconnected-(GND-*D10-Pad10)") (class "Default")
      (node (ref "GND") (pin "10") (pinfunction "*D10_10") (pintype "bidirectional"))
    )
    (net (code "86") (name "unconnected-(GND-*D11-Pad11)") (class "Default")
      (node (ref "GND") (pin "11") (pinfunction "*D11_11") (pintype "bidirectional"))
    )
    (net (code "87") (name "unconnected-(GND-D4-Pad4)") (class "Default")
      (node (ref "GND") (pin "4") (pinfunction "D4_4") (pintype "bidirectional"))
    )
    (net (code "88") (name "unconnected-(GND-D7-Pad7)") (class "Default")
      (node (ref "GND") (pin "7") (pinfunction "D7_7") (pintype "bidirectional"))
    )
    (net (code "89") (name "unconnected-(GND-D8-Pad8)") (class "Default")
      (node (ref "GND") (pin "8") (pinfunction "D8_8") (pintype "bidirectional"))
    )
    (net (code "90") (name "unconnected-(GND-D12-Pad12)") (class "Default")
      (node (ref "GND") (pin "12") (pinfunction "D12_12") (pintype "bidirectional"))
    )
    (net (code "91") (name "unconnected-(GND-D13-Pad13)") (class "Default")
      (node (ref "GND") (pin "13") (pinfunction "D13_13") (pintype "bidirectional"))
    )
    (net (code "92") (name "unconnected-(GND-Pad3.3V)") (class "Default")
      (node (ref "GND") (pin "3.3V") (pinfunction "3.3V_3.3V") (pintype "bidirectional"))
    )
    (net (code "93") (name "unconnected-(GND-PadA0)") (class "Default")
      (node (ref "GND") (pin "A0") (pinfunction "A0_A0") (pintype "bidirectional"))
    )
    (net (code "94") (name "unconnected-(GND-PadA2)") (class "Default")
      (node (ref "GND") (pin "A2") (pinfunction "A2_A2") (pintype "bidirectional"))
    )
    (net (code "95") (name "unconnected-(GND-PadA3)") (class "Default")
      (node (ref "GND") (pin "A3") (pinfunction "A3_A3") (pintype "bidirectional"))
    )
    (net (code "96") (name "unconnected-(GND-PadAREF)") (class "Default")
      (node (ref "GND") (pin "AREF") (pinfunction "AREF_AREF") (pintype "bidirectional"))
    )
    (net (code "97") (name "unconnected-(GND-RES-PadRESET)") (class "Default")
      (node (ref "GND") (pin "RESET") (pinfunction "RES_RESET") (pintype "bidirectional"))
    )
    (net (code "98") (name "unconnected-(GND-RX-Pad0)") (class "Default")
      (node (ref "GND") (pin "0") (pinfunction "RX_0") (pintype "bidirectional"))
    )
    (net (code "99") (name "unconnected-(GND-TX-Pad1)") (class "Default")
      (node (ref "GND") (pin "1") (pinfunction "TX_1") (pintype "bidirectional"))
    )
    (net (code "100") (name "unconnected-(IC2-INTA-Pad20)") (class "Default")
      (node (ref "IC2") (pin "20") (pinfunction "INTA_20") (pintype "output"))
    )
    (net (code "101") (name "unconnected-(IC2-INTB-Pad19)") (class "Default")
      (node (ref "IC2") (pin "19") (pinfunction "INTB_19") (pintype "output"))
    )
    (net (code "102") (name "unconnected-(K1B-O-PadO1)") (class "Default")
      (node (ref "K1") (pin "O1") (pinfunction "O_O1") (pintype "passive"))
    )
    (net (code "103") (name "unconnected-(K1C-O-PadO2)") (class "Default")
      (node (ref "K1") (pin "O2") (pinfunction "O_O2") (pintype "passive"))
    )
    (net (code "104") (name "unconnected-(K2B-O-PadO1)") (class "Default")
      (node (ref "K2") (pin "O1") (pinfunction "O_O1") (pintype "passive"))
    )
    (net (code "105") (name "unconnected-(K2C-O-PadO2)") (class "Default")
      (node (ref "K2") (pin "O2") (pinfunction "O_O2") (pintype "passive"))
    )
    (net (code "106") (name "unconnected-(K3B-O-PadO1)") (class "Default")
      (node (ref "K3") (pin "O1") (pinfunction "O_O1") (pintype "passive"))
    )
    (net (code "107") (name "unconnected-(K3C-O-PadO2)") (class "Default")
      (node (ref "K3") (pin "O2") (pinfunction "O_O2") (pintype "passive"))
    )
    (net (code "108") (name "unconnected-(K4B-O-PadO1)") (class "Default")
      (node (ref "K4") (pin "O1") (pinfunction "O_O1") (pintype "passive"))
    )
    (net (code "109") (name "unconnected-(K4C-O-PadO2)") (class "Default")
      (node (ref "K4") (pin "O2") (pinfunction "O_O2") (pintype "passive"))
    )
    (net (code "110") (name "unconnected-(K5B-O-PadO1)") (class "Default")
      (node (ref "K5") (pin "O1") (pinfunction "O_O1") (pintype "passive"))
    )
    (net (code "111") (name "unconnected-(K5C-O-PadO2)") (class "Default")
      (node (ref "K5") (pin "O2") (pinfunction "O_O2") (pintype "passive"))
    )
    (net (code "112") (name "unconnected-(K6B-O-PadO1)") (class "Default")
      (node (ref "K6") (pin "O1") (pinfunction "O_O1") (pintype "passive"))
    )
    (net (code "113") (name "unconnected-(K6C-O-PadO2)") (class "Default")
      (node (ref "K6") (pin "O2") (pinfunction "O_O2") (pintype "passive"))
    )
    (net (code "114") (name "unconnected-(K7B-O-PadO1)") (class "Default")
      (node (ref "K7") (pin "O1") (pinfunction "O_O1") (pintype "passive"))
    )
    (net (code "115") (name "unconnected-(K7C-O-PadO2)") (class "Default")
      (node (ref "K7") (pin "O2") (pinfunction "O_O2") (pintype "passive"))
    )
    (net (code "116") (name "unconnected-(K8B-O-PadO1)") (class "Default")
      (node (ref "K8") (pin "O1") (pinfunction "O_O1") (pintype "passive"))
    )
    (net (code "117") (name "unconnected-(K8C-O-PadO2)") (class "Default")
      (node (ref "K8") (pin "O2") (pinfunction "O_O2") (pintype "passive"))
    )
    (net (code "118") (name "unconnected-(SERIAL-Pad5)") (class "Default")
      (node (ref "SERIAL") (pin "5") (pinfunction "5_5") (pintype "passive"))
    )
    (net (code "119") (name "unconnected-(SERIAL-Pad6)") (class "Default")
      (node (ref "SERIAL") (pin "6") (pinfunction "6_6") (pintype "passive"))
    )
    (net (code "120") (name "unconnected-(SERIAL-Pad7)") (class "Default")
      (node (ref "SERIAL") (pin "7") (pinfunction "7_7") (pintype "passive"))
    )
    (net (code "121") (name "unconnected-(SERIAL-Pad8)") (class "Default")
      (node (ref "SERIAL") (pin "8") (pinfunction "8_8") (pintype "passive"))
    )
  )
)
